# IRQF103C8.net
KiCad netlist of a schematic drawn in EAGLE
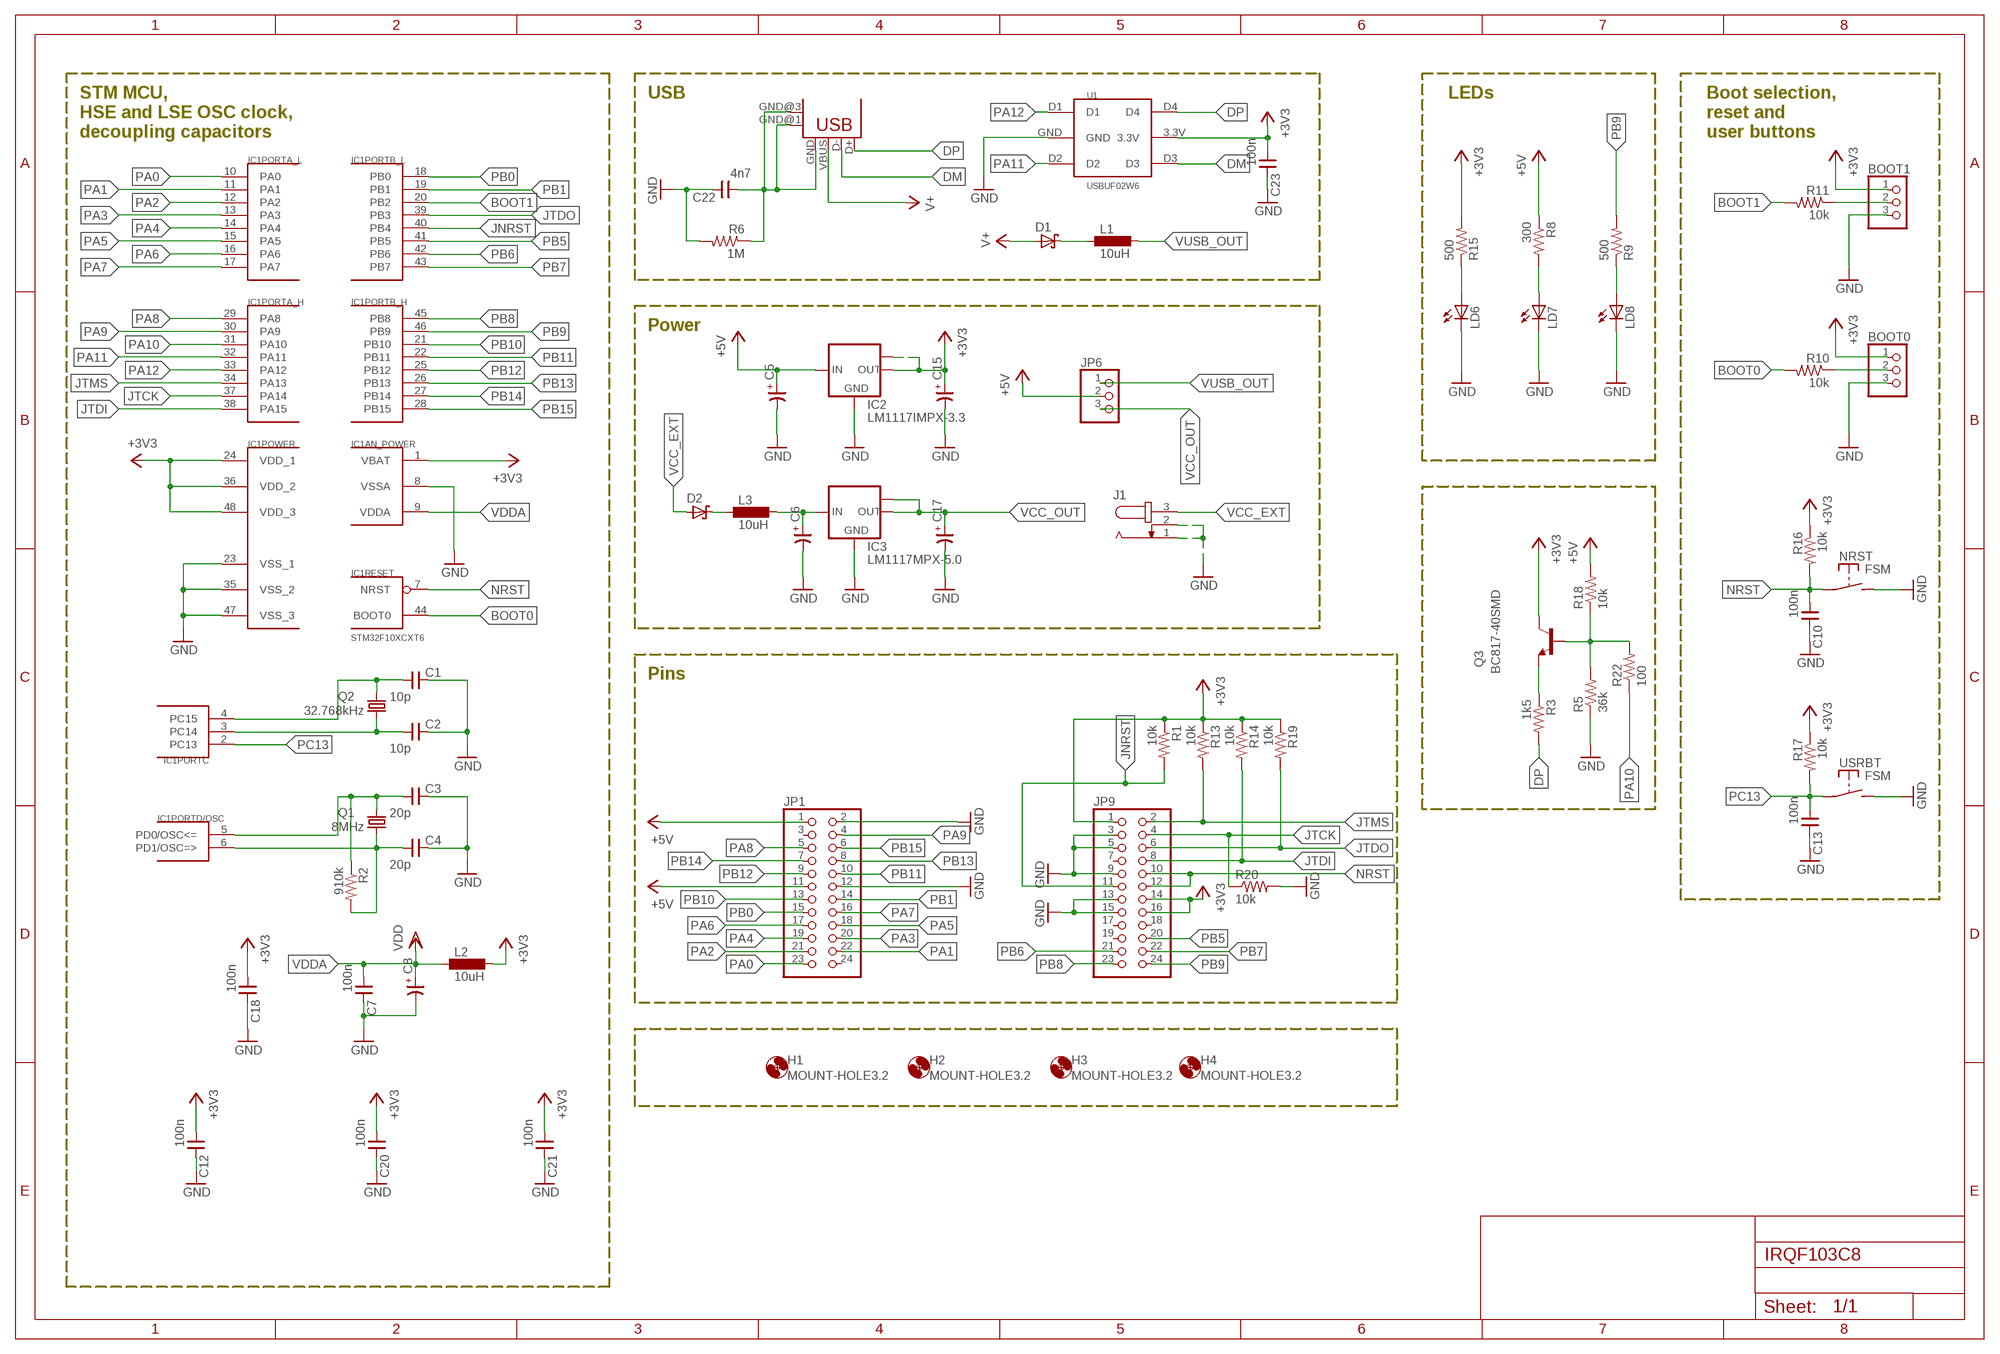
[diagram p0: schematic, sheet 1]

(export (version "E")
  (design (tool "Eeschema 10.0.6"))
  (components
    (comp (ref "BOOT0")
      (value "PINHD-1X3")
      (footprint "eagle-import:1X03")
      (libsource (lib "eagle-import") (part "PINHD-1X3"))
    )
    (comp (ref "BOOT1")
      (value "PINHD-1X3")
      (footprint "eagle-import:1X03")
      (libsource (lib "eagle-import") (part "PINHD-1X3"))
    )
    (comp (ref "C1")
      (value "10p")
      (footprint "eagle-import:0805")
      (libsource (lib "eagle-import") (part "CNP-0805"))
    )
    (comp (ref "C2")
      (value "10p")
      (footprint "eagle-import:0805")
      (libsource (lib "eagle-import") (part "CNP-0805"))
    )
    (comp (ref "C3")
      (value "20p")
      (footprint "eagle-import:0805")
      (libsource (lib "eagle-import") (part "CNP-0805"))
    )
    (comp (ref "C4")
      (value "20p")
      (footprint "eagle-import:0805")
      (libsource (lib "eagle-import") (part "CNP-0805"))
    )
    (comp (ref "C5")
      (value "CP-3258-TE-B")
      (footprint "eagle-import:3528-TE-B")
      (libsource (lib "eagle-import") (part "CP-3258-TE-B"))
    )
    (comp (ref "C6")
      (value "CP-3258-TE-B")
      (footprint "eagle-import:3528-TE-B")
      (libsource (lib "eagle-import") (part "CP-3258-TE-B"))
    )
    (comp (ref "C7")
      (value "100n")
      (footprint "eagle-import:0805")
      (libsource (lib "eagle-import") (part "CNP-0805"))
    )
    (comp (ref "C8")
      (value "CP-3216")
      (footprint "eagle-import:3216_T")
      (libsource (lib "eagle-import") (part "CP-3216"))
    )
    (comp (ref "C10")
      (value "100n")
      (footprint "eagle-import:0805")
      (libsource (lib "eagle-import") (part "CNP-0805"))
    )
    (comp (ref "C12")
      (value "100n")
      (footprint "eagle-import:0805")
      (libsource (lib "eagle-import") (part "CNP-0805"))
    )
    (comp (ref "C13")
      (value "100n")
      (footprint "eagle-import:0805")
      (libsource (lib "eagle-import") (part "CNP-0805"))
    )
    (comp (ref "C15")
      (value "CP-3216-TE-A")
      (footprint "eagle-import:3216-TE-A")
      (libsource (lib "eagle-import") (part "CP-3216-TE-A"))
    )
    (comp (ref "C17")
      (value "CP-3216-TE-A")
      (footprint "eagle-import:3216-TE-A")
      (libsource (lib "eagle-import") (part "CP-3216-TE-A"))
    )
    (comp (ref "C18")
      (value "100n")
      (footprint "eagle-import:0805")
      (libsource (lib "eagle-import") (part "CNP-0805"))
    )
    (comp (ref "C20")
      (value "100n")
      (footprint "eagle-import:0805")
      (libsource (lib "eagle-import") (part "CNP-0805"))
    )
    (comp (ref "C21")
      (value "100n")
      (footprint "eagle-import:0805")
      (libsource (lib "eagle-import") (part "CNP-0805"))
    )
    (comp (ref "C22")
      (value "4n7")
      (footprint "eagle-import:0805")
      (libsource (lib "eagle-import") (part "CNP-0805"))
    )
    (comp (ref "C23")
      (value "100n")
      (footprint "eagle-import:0805")
      (libsource (lib "eagle-import") (part "CNP-0805"))
    )
    (comp (ref "D1")
      (value "SCHOTTKY_SMA")
      (footprint "eagle-import:DIOM5326X292N")
      (libsource (lib "eagle-import") (part "SCHOTTKY_SMA"))
    )
    (comp (ref "D2")
      (value "SCHOTTKY_SMA")
      (footprint "eagle-import:DIOM5326X292N")
      (libsource (lib "eagle-import") (part "SCHOTTKY_SMA"))
    )
    (comp (ref "H1")
      (value "MOUNT-HOLE3.2")
      (footprint "eagle-import:3,2")
      (libsource (lib "eagle-import") (part "MOUNT-HOLE3.2"))
    )
    (comp (ref "H2")
      (value "MOUNT-HOLE3.2")
      (footprint "eagle-import:3,2")
      (libsource (lib "eagle-import") (part "MOUNT-HOLE3.2"))
    )
    (comp (ref "H3")
      (value "MOUNT-HOLE3.2")
      (footprint "eagle-import:3,2")
      (libsource (lib "eagle-import") (part "MOUNT-HOLE3.2"))
    )
    (comp (ref "H4")
      (value "MOUNT-HOLE3.2")
      (footprint "eagle-import:3,2")
      (libsource (lib "eagle-import") (part "MOUNT-HOLE3.2"))
    )
    (comp (ref "IC1")
      (value "STM32F10XCXT6")
      (footprint "eagle-import:TQFP48")
      (libsource (lib "eagle-import") (part "STM32F10XCXT6"))
    )
    (comp (ref "IC2")
      (value "LM1117IMPX-3.3")
      (footprint "eagle-import:SOT223")
      (libsource (lib "eagle-import") (part "LM1117IMPX-3.3"))
    )
    (comp (ref "IC3")
      (value "LM1117MPX-5.0")
      (footprint "eagle-import:SOT223")
      (libsource (lib "eagle-import") (part "LM1117MPX-5.0"))
    )
    (comp (ref "J1")
      (value "JACK-PLUG1")
      (footprint "eagle-import:SPC4078")
      (libsource (lib "eagle-import") (part "JACK-PLUG1"))
    )
    (comp (ref "JP1")
      (value "PINHD-2X12")
      (footprint "eagle-import:2X12")
      (libsource (lib "eagle-import") (part "PINHD-2X12"))
    )
    (comp (ref "JP6")
      (value "PINHD-1X3")
      (footprint "eagle-import:1X03")
      (libsource (lib "eagle-import") (part "PINHD-1X3"))
    )
    (comp (ref "JP9")
      (value "PINHD-2X12")
      (footprint "eagle-import:2X12")
      (libsource (lib "eagle-import") (part "PINHD-2X12"))
    )
    (comp (ref "L1")
      (value "10uH")
      (footprint "eagle-import:INDC1608X95N")
      (libsource (lib "eagle-import") (part "INDUCTOR_0603"))
    )
    (comp (ref "L2")
      (value "10uH")
      (footprint "eagle-import:INDC1608X95N")
      (libsource (lib "eagle-import") (part "INDUCTOR_0603"))
    )
    (comp (ref "L3")
      (value "10uH")
      (footprint "eagle-import:INDC1608X95N")
      (libsource (lib "eagle-import") (part "INDUCTOR_0603"))
    )
    (comp (ref "LD6")
      (value "LEDCHIPLED_0805")
      (footprint "eagle-import:CHIPLED_0805")
      (libsource (lib "eagle-import") (part "LEDCHIPLED_0805"))
    )
    (comp (ref "LD7")
      (value "LEDCHIPLED_0805")
      (footprint "eagle-import:CHIPLED_0805")
      (libsource (lib "eagle-import") (part "LEDCHIPLED_0805"))
    )
    (comp (ref "LD8")
      (value "LEDCHIPLED_0805")
      (footprint "eagle-import:CHIPLED_0805")
      (libsource (lib "eagle-import") (part "LEDCHIPLED_0805"))
    )
    (comp (ref "NRST")
      (value "FSM")
      (footprint "eagle-import:FSM")
      (libsource (lib "eagle-import") (part "FSM"))
    )
    (comp (ref "Q1")
      (value "8MHz")
      (footprint "eagle-import:HC49_S")
      (libsource (lib "eagle-import") (part "CRYTALHC49S"))
    )
    (comp (ref "Q2")
      (value "32.768kHz")
      (footprint "eagle-import:TC26H")
      (libsource (lib "eagle-import") (part "CRYTALTC26H"))
    )
    (comp (ref "Q3")
      (value "BC817-40SMD")
      (footprint "eagle-import:SOT23-BEC")
      (libsource (lib "eagle-import") (part "BC817SMD-40"))
    )
    (comp (ref "R1")
      (value "10k")
      (footprint "eagle-import:M0805")
      (libsource (lib "eagle-import") (part "R-US_M0805"))
    )
    (comp (ref "R2")
      (value "910k")
      (footprint "eagle-import:M0805")
      (libsource (lib "eagle-import") (part "R-US_M0805"))
    )
    (comp (ref "R3")
      (value "1k5")
      (footprint "eagle-import:M0805")
      (libsource (lib "eagle-import") (part "R-US_M0805"))
    )
    (comp (ref "R5")
      (value "36k")
      (footprint "eagle-import:M0805")
      (libsource (lib "eagle-import") (part "R-US_M0805"))
    )
    (comp (ref "R6")
      (value "1M")
      (footprint "eagle-import:M0805")
      (libsource (lib "eagle-import") (part "R-US_M0805"))
    )
    (comp (ref "R8")
      (value "300")
      (footprint "eagle-import:M0805")
      (libsource (lib "eagle-import") (part "R-US_M0805"))
    )
    (comp (ref "R9")
      (value "500")
      (footprint "eagle-import:M0805")
      (libsource (lib "eagle-import") (part "R-US_M0805"))
    )
    (comp (ref "R10")
      (value "10k")
      (footprint "eagle-import:M0805")
      (libsource (lib "eagle-import") (part "R-US_M0805"))
    )
    (comp (ref "R11")
      (value "10k")
      (footprint "eagle-import:M0805")
      (libsource (lib "eagle-import") (part "R-US_M0805"))
    )
    (comp (ref "R13")
      (value "10k")
      (footprint "eagle-import:M0805")
      (libsource (lib "eagle-import") (part "R-US_M0805"))
    )
    (comp (ref "R14")
      (value "10k")
      (footprint "eagle-import:M0805")
      (libsource (lib "eagle-import") (part "R-US_M0805"))
    )
    (comp (ref "R15")
      (value "500")
      (footprint "eagle-import:M0805")
      (libsource (lib "eagle-import") (part "R-US_M0805"))
    )
    (comp (ref "R16")
      (value "10k")
      (footprint "eagle-import:M0805")
      (libsource (lib "eagle-import") (part "R-US_M0805"))
    )
    (comp (ref "R17")
      (value "10k")
      (footprint "eagle-import:M0805")
      (libsource (lib "eagle-import") (part "R-US_M0805"))
    )
    (comp (ref "R18")
      (value "10k")
      (footprint "eagle-import:M0805")
      (libsource (lib "eagle-import") (part "R-US_M0805"))
    )
    (comp (ref "R19")
      (value "10k")
      (footprint "eagle-import:M0805")
      (libsource (lib "eagle-import") (part "R-US_M0805"))
    )
    (comp (ref "R20")
      (value "10k")
      (footprint "eagle-import:M0805")
      (libsource (lib "eagle-import") (part "R-US_M0805"))
    )
    (comp (ref "R22")
      (value "100")
      (footprint "eagle-import:M0805")
      (libsource (lib "eagle-import") (part "R-US_M0805"))
    )
    (comp (ref "U1")
      (value "USBUF02W6")
      (footprint "eagle-import:SOT23-6L")
      (libsource (lib "eagle-import") (part "USBUF02W6"))
    )
    (comp (ref "USB1")
      (value "USB-MB-S")
      (footprint "eagle-import:USB-MB-S")
      (libsource (lib "eagle-import") (part "USB-MB-S"))
    )
    (comp (ref "USRBT")
      (value "FSM")
      (footprint "eagle-import:FSM")
      (libsource (lib "eagle-import") (part "FSM"))
    )
  )
  (nets
    (net (code "1") (name "+3V3") (class "Default")
      (node (ref "BOOT0") (pin "1") (pinfunction "1_1") (pintype "passive"))
      (node (ref "BOOT1") (pin "1") (pinfunction "1_1") (pintype "passive"))
      (node (ref "C12") (pin "1") (pinfunction "1_1") (pintype "passive"))
      (node (ref "C15") (pin "+") (pinfunction "+_+") (pintype "passive"))
      (node (ref "C18") (pin "1") (pinfunction "1_1") (pintype "passive"))
      (node (ref "C20") (pin "1") (pinfunction "1_1") (pintype "passive"))
      (node (ref "C21") (pin "1") (pinfunction "1_1") (pintype "passive"))
      (node (ref "C23") (pin "1") (pinfunction "1_1") (pintype "passive"))
      (node (ref "IC1") (pin "1") (pinfunction "VBAT_1") (pintype "power_in"))
      (node (ref "IC1") (pin "24") (pinfunction "VDD_1_24") (pintype "power_in"))
      (node (ref "IC1") (pin "36") (pinfunction "VDD_2_36") (pintype "power_in"))
      (node (ref "IC1") (pin "48") (pinfunction "VDD_3_48") (pintype "power_in"))
      (node (ref "IC2") (pin "2") (pinfunction "OUT_2") (pintype "passive"))
      (node (ref "IC2") (pin "TAB") (pinfunction "OUT1_TAB") (pintype "passive"))
      (node (ref "JP9") (pin "1") (pinfunction "1_1") (pintype "passive"))
      (node (ref "JP9") (pin "14") (pinfunction "14_14") (pintype "passive"))
      (node (ref "JP9") (pin "16") (pinfunction "16_16") (pintype "passive"))
      (node (ref "L2") (pin "2") (pinfunction "2_2") (pintype "passive"))
      (node (ref "Q3") (pin "C") (pinfunction "C_C") (pintype "passive"))
      (node (ref "R1") (pin "1") (pinfunction "1_1") (pintype "passive"))
      (node (ref "R13") (pin "1") (pinfunction "1_1") (pintype "passive"))
      (node (ref "R14") (pin "1") (pinfunction "1_1") (pintype "passive"))
      (node (ref "R15") (pin "2") (pinfunction "2_2") (pintype "passive"))
      (node (ref "R16") (pin "1") (pinfunction "1_1") (pintype "passive"))
      (node (ref "R17") (pin "1") (pinfunction "1_1") (pintype "passive"))
      (node (ref "R19") (pin "1") (pinfunction "1_1") (pintype "passive"))
      (node (ref "U1") (pin "3.3V") (pinfunction "3.3V_3.3V") (pintype "bidirectional"))
    )
    (net (code "2") (name "+5V") (class "Default")
      (node (ref "C5") (pin "+") (pinfunction "+_+") (pintype "passive"))
      (node (ref "IC2") (pin "3") (pinfunction "IN_3") (pintype "input"))
      (node (ref "JP1") (pin "1") (pinfunction "1_1") (pintype "passive"))
      (node (ref "JP1") (pin "11") (pinfunction "11_11") (pintype "passive"))
      (node (ref "JP6") (pin "2") (pinfunction "2_2") (pintype "passive"))
      (node (ref "R18") (pin "2") (pinfunction "2_2") (pintype "passive"))
      (node (ref "R8") (pin "1") (pinfunction "1_1") (pintype "passive"))
    )
    (net (code "3") (name "BOOT0") (class "Default")
      (node (ref "IC1") (pin "44") (pinfunction "BOOT0_44") (pintype "input"))
      (node (ref "R10") (pin "2") (pinfunction "2_2") (pintype "passive"))
    )
    (net (code "4") (name "BOOT1") (class "Default")
      (node (ref "IC1") (pin "20") (pinfunction "PB2_20") (pintype "bidirectional"))
      (node (ref "R11") (pin "2") (pinfunction "2_2") (pintype "passive"))
    )
    (net (code "5") (name "DM") (class "Default")
      (node (ref "U1") (pin "D3") (pinfunction "D3_D3") (pintype "bidirectional"))
      (node (ref "USB1") (pin "D-") (pinfunction "D-_D-") (pintype "bidirectional"))
    )
    (net (code "6") (name "DP") (class "Default")
      (node (ref "R3") (pin "2") (pinfunction "2_2") (pintype "passive"))
      (node (ref "U1") (pin "D4") (pinfunction "D4_D4") (pintype "bidirectional"))
      (node (ref "USB1") (pin "D+") (pinfunction "D+_D+") (pintype "bidirectional"))
    )
    (net (code "7") (name "GND") (class "Default")
      (node (ref "BOOT0") (pin "3") (pinfunction "3_3") (pintype "passive"))
      (node (ref "BOOT1") (pin "3") (pinfunction "3_3") (pintype "passive"))
      (node (ref "C1") (pin "2") (pinfunction "2_2") (pintype "passive"))
      (node (ref "C10") (pin "2") (pinfunction "2_2") (pintype "passive"))
      (node (ref "C12") (pin "2") (pinfunction "2_2") (pintype "passive"))
      (node (ref "C13") (pin "2") (pinfunction "2_2") (pintype "passive"))
      (node (ref "C15") (pin "-") (pinfunction "-_-") (pintype "passive"))
      (node (ref "C17") (pin "-") (pinfunction "-_-") (pintype "passive"))
      (node (ref "C18") (pin "2") (pinfunction "2_2") (pintype "passive"))
      (node (ref "C2") (pin "2") (pinfunction "2_2") (pintype "passive"))
      (node (ref "C20") (pin "2") (pinfunction "2_2") (pintype "passive"))
      (node (ref "C21") (pin "2") (pinfunction "2_2") (pintype "passive"))
      (node (ref "C22") (pin "2") (pinfunction "2_2") (pintype "passive"))
      (node (ref "C23") (pin "2") (pinfunction "2_2") (pintype "passive"))
      (node (ref "C3") (pin "2") (pinfunction "2_2") (pintype "passive"))
      (node (ref "C4") (pin "2") (pinfunction "2_2") (pintype "passive"))
      (node (ref "C5") (pin "-") (pinfunction "-_-") (pintype "passive"))
      (node (ref "C6") (pin "-") (pinfunction "-_-") (pintype "passive"))
      (node (ref "C7") (pin "2") (pinfunction "2_2") (pintype "passive"))
      (node (ref "C8") (pin "-") (pinfunction "-_-") (pintype "passive"))
      (node (ref "IC1") (pin "23") (pinfunction "VSS_1_23") (pintype "power_in"))
      (node (ref "IC1") (pin "35") (pinfunction "VSS_2_35") (pintype "power_in"))
      (node (ref "IC1") (pin "47") (pinfunction "VSS_3_47") (pintype "power_in"))
      (node (ref "IC1") (pin "8") (pinfunction "VSSA_8") (pintype "power_in"))
      (node (ref "IC2") (pin "1") (pinfunction "GND_1") (pintype "input"))
      (node (ref "IC3") (pin "1") (pinfunction "GND_1") (pintype "input"))
      (node (ref "J1") (pin "1") (pinfunction "1_1") (pintype "passive"))
      (node (ref "J1") (pin "2") (pinfunction "2_2") (pintype "passive"))
      (node (ref "JP1") (pin "12") (pinfunction "12_12") (pintype "passive"))
      (node (ref "JP1") (pin "2") (pinfunction "2_2") (pintype "passive"))
      (node (ref "JP9") (pin "13") (pinfunction "13_13") (pintype "passive"))
      (node (ref "JP9") (pin "15") (pinfunction "15_15") (pintype "passive"))
      (node (ref "JP9") (pin "3") (pinfunction "3_3") (pintype "passive"))
      (node (ref "JP9") (pin "5") (pinfunction "5_5") (pintype "passive"))
      (node (ref "JP9") (pin "9") (pinfunction "9_9") (pintype "passive"))
      (node (ref "LD6") (pin "C") (pinfunction "C_C") (pintype "passive"))
      (node (ref "LD7") (pin "C") (pinfunction "C_C") (pintype "passive"))
      (node (ref "LD8") (pin "C") (pinfunction "C_C") (pintype "passive"))
      (node (ref "NRST") (pin "P$2") (pinfunction "S_P$2") (pintype "passive"))
      (node (ref "R20") (pin "2") (pinfunction "2_2") (pintype "passive"))
      (node (ref "R5") (pin "1") (pinfunction "1_1") (pintype "passive"))
      (node (ref "R6") (pin "2") (pinfunction "2_2") (pintype "passive"))
      (node (ref "U1") (pin "GND") (pinfunction "GND_GND") (pintype "bidirectional"))
      (node (ref "USRBT") (pin "P$2") (pinfunction "S_P$2") (pintype "passive"))
    )
    (net (code "8") (name "JNRST") (class "Default")
      (node (ref "IC1") (pin "40") (pinfunction "PB4_40") (pintype "bidirectional"))
      (node (ref "JP9") (pin "11") (pinfunction "11_11") (pintype "passive"))
      (node (ref "R1") (pin "2") (pinfunction "2_2") (pintype "passive"))
    )
    (net (code "9") (name "JTCK") (class "Default")
      (node (ref "IC1") (pin "37") (pinfunction "PA14_37") (pintype "bidirectional"))
      (node (ref "JP9") (pin "4") (pinfunction "4_4") (pintype "passive"))
      (node (ref "R20") (pin "1") (pinfunction "1_1") (pintype "passive"))
    )
    (net (code "10") (name "JTDI") (class "Default")
      (node (ref "IC1") (pin "38") (pinfunction "PA15_38") (pintype "bidirectional"))
      (node (ref "JP9") (pin "8") (pinfunction "8_8") (pintype "passive"))
      (node (ref "R14") (pin "2") (pinfunction "2_2") (pintype "passive"))
    )
    (net (code "11") (name "JTDO") (class "Default")
      (node (ref "IC1") (pin "39") (pinfunction "PB3_39") (pintype "bidirectional"))
      (node (ref "JP9") (pin "6") (pinfunction "6_6") (pintype "passive"))
      (node (ref "R19") (pin "2") (pinfunction "2_2") (pintype "passive"))
    )
    (net (code "12") (name "JTMS") (class "Default")
      (node (ref "IC1") (pin "34") (pinfunction "PA13_34") (pintype "bidirectional"))
      (node (ref "JP9") (pin "2") (pinfunction "2_2") (pintype "passive"))
      (node (ref "R13") (pin "2") (pinfunction "2_2") (pintype "passive"))
    )
    (net (code "13") (name "NRST") (class "Default")
      (node (ref "C10") (pin "1") (pinfunction "1_1") (pintype "passive"))
      (node (ref "IC1") (pin "7") (pinfunction "NRST_7") (pintype "input"))
      (node (ref "JP9") (pin "10") (pinfunction "10_10") (pintype "passive"))
      (node (ref "JP9") (pin "12") (pinfunction "12_12") (pintype "passive"))
      (node (ref "NRST") (pin "P$1") (pinfunction "P_P$1") (pintype "passive"))
      (node (ref "R16") (pin "2") (pinfunction "2_2") (pintype "passive"))
    )
    (net (code "14") (name "Net-(BOOT0-Pad2)") (class "Default")
      (node (ref "BOOT0") (pin "2") (pinfunction "2_2") (pintype "passive"))
      (node (ref "R10") (pin "1") (pinfunction "1_1") (pintype "passive"))
    )
    (net (code "15") (name "Net-(BOOT1-Pad2)") (class "Default")
      (node (ref "BOOT1") (pin "2") (pinfunction "2_2") (pintype "passive"))
      (node (ref "R11") (pin "1") (pinfunction "1_1") (pintype "passive"))
    )
    (net (code "16") (name "Net-(C22-Pad1)") (class "Default")
      (node (ref "C22") (pin "1") (pinfunction "1_1") (pintype "passive"))
      (node (ref "R6") (pin "1") (pinfunction "1_1") (pintype "passive"))
      (node (ref "USB1") (pin "GND") (pinfunction "GND_GND") (pintype "bidirectional"))
      (node (ref "USB1") (pin "GND@1") (pinfunction "GND_GND@1") (pintype "bidirectional"))
      (node (ref "USB1") (pin "GND@3") (pinfunction "GND_GND@3") (pintype "bidirectional"))
    )
    (net (code "17") (name "Net-(D1-PadK)") (class "Default")
      (node (ref "D1") (pin "K") (pinfunction "K_K") (pintype "passive"))
      (node (ref "L1") (pin "1") (pinfunction "1_1") (pintype "passive"))
    )
    (net (code "18") (name "Net-(D2-PadK)") (class "Default")
      (node (ref "D2") (pin "K") (pinfunction "K_K") (pintype "passive"))
      (node (ref "L3") (pin "1") (pinfunction "1_1") (pintype "passive"))
    )
    (net (code "19") (name "Net-(IC1F-PC14)") (class "Default")
      (node (ref "C2") (pin "1") (pinfunction "1_1") (pintype "passive"))
      (node (ref "IC1") (pin "3") (pinfunction "PC14_3") (pintype "bidirectional"))
      (node (ref "Q2") (pin "1") (pinfunction "1_1") (pintype "passive"))
    )
    (net (code "20") (name "Net-(IC1F-PC15)") (class "Default")
      (node (ref "C1") (pin "1") (pinfunction "1_1") (pintype "passive"))
      (node (ref "IC1") (pin "4") (pinfunction "PC15_4") (pintype "bidirectional"))
      (node (ref "Q2") (pin "2") (pinfunction "2_2") (pintype "passive"))
    )
    (net (code "21") (name "Net-(IC1G-PD0{slash}OSC<=)") (class "Default")
      (node (ref "C3") (pin "1") (pinfunction "1_1") (pintype "passive"))
      (node (ref "IC1") (pin "5") (pinfunction "PD0/OSC<=_5") (pintype "bidirectional"))
      (node (ref "Q1") (pin "2") (pinfunction "2_2") (pintype "passive"))
      (node (ref "R2") (pin "1") (pinfunction "1_1") (pintype "passive"))
    )
    (net (code "22") (name "Net-(IC1G-PD1{slash}OSC=>)") (class "Default")
      (node (ref "C4") (pin "1") (pinfunction "1_1") (pintype "passive"))
      (node (ref "IC1") (pin "6") (pinfunction "PD1/OSC=>_6") (pintype "bidirectional"))
      (node (ref "Q1") (pin "1") (pinfunction "1_1") (pintype "passive"))
      (node (ref "R2") (pin "2") (pinfunction "2_2") (pintype "passive"))
    )
    (net (code "23") (name "Net-(IC3-IN)") (class "Default")
      (node (ref "C6") (pin "+") (pinfunction "+_+") (pintype "passive"))
      (node (ref "IC3") (pin "3") (pinfunction "IN_3") (pintype "input"))
      (node (ref "L3") (pin "2") (pinfunction "2_2") (pintype "passive"))
    )
    (net (code "24") (name "Net-(LD6-PadA)") (class "Default")
      (node (ref "LD6") (pin "A") (pinfunction "A_A") (pintype "passive"))
      (node (ref "R15") (pin "1") (pinfunction "1_1") (pintype "passive"))
    )
    (net (code "25") (name "Net-(LD7-PadA)") (class "Default")
      (node (ref "LD7") (pin "A") (pinfunction "A_A") (pintype "passive"))
      (node (ref "R8") (pin "2") (pinfunction "2_2") (pintype "passive"))
    )
    (net (code "26") (name "Net-(LD8-PadA)") (class "Default")
      (node (ref "LD8") (pin "A") (pinfunction "A_A") (pintype "passive"))
      (node (ref "R9") (pin "1") (pinfunction "1_1") (pintype "passive"))
    )
    (net (code "27") (name "Net-(Q3-PadB)") (class "Default")
      (node (ref "Q3") (pin "B") (pinfunction "B_B") (pintype "passive"))
      (node (ref "R18") (pin "1") (pinfunction "1_1") (pintype "passive"))
      (node (ref "R22") (pin "2") (pinfunction "2_2") (pintype "passive"))
      (node (ref "R5") (pin "2") (pinfunction "2_2") (pintype "passive"))
    )
    (net (code "28") (name "Net-(Q3-PadE)") (class "Default")
      (node (ref "Q3") (pin "E") (pinfunction "E_E") (pintype "passive"))
      (node (ref "R3") (pin "1") (pinfunction "1_1") (pintype "passive"))
    )
    (net (code "29") (name "PA0") (class "Default")
      (node (ref "IC1") (pin "10") (pinfunction "PA0_10") (pintype "bidirectional"))
      (node (ref "JP1") (pin "23") (pinfunction "23_23") (pintype "passive"))
    )
    (net (code "30") (name "PA1") (class "Default")
      (node (ref "IC1") (pin "11") (pinfunction "PA1_11") (pintype "bidirectional"))
      (node (ref "JP1") (pin "22") (pinfunction "22_22") (pintype "passive"))
    )
    (net (code "31") (name "PA2") (class "Default")
      (node (ref "IC1") (pin "12") (pinfunction "PA2_12") (pintype "bidirectional"))
      (node (ref "JP1") (pin "21") (pinfunction "21_21") (pintype "passive"))
    )
    (net (code "32") (name "PA3") (class "Default")
      (node (ref "IC1") (pin "13") (pinfunction "PA3_13") (pintype "bidirectional"))
      (node (ref "JP1") (pin "20") (pinfunction "20_20") (pintype "passive"))
    )
    (net (code "33") (name "PA4") (class "Default")
      (node (ref "IC1") (pin "14") (pinfunction "PA4_14") (pintype "bidirectional"))
      (node (ref "JP1") (pin "19") (pinfunction "19_19") (pintype "passive"))
    )
    (net (code "34") (name "PA5") (class "Default")
      (node (ref "IC1") (pin "15") (pinfunction "PA5_15") (pintype "bidirectional"))
      (node (ref "JP1") (pin "18") (pinfunction "18_18") (pintype "passive"))
    )
    (net (code "35") (name "PA6") (class "Default")
      (node (ref "IC1") (pin "16") (pinfunction "PA6_16") (pintype "bidirectional"))
      (node (ref "JP1") (pin "17") (pinfunction "17_17") (pintype "passive"))
    )
    (net (code "36") (name "PA7") (class "Default")
      (node (ref "IC1") (pin "17") (pinfunction "PA7_17") (pintype "bidirectional"))
      (node (ref "JP1") (pin "16") (pinfunction "16_16") (pintype "passive"))
    )
    (net (code "37") (name "PA8") (class "Default")
      (node (ref "IC1") (pin "29") (pinfunction "PA8_29") (pintype "bidirectional"))
      (node (ref "JP1") (pin "5") (pinfunction "5_5") (pintype "passive"))
    )
    (net (code "38") (name "PA9") (class "Default")
      (node (ref "IC1") (pin "30") (pinfunction "PA9_30") (pintype "bidirectional"))
      (node (ref "JP1") (pin "4") (pinfunction "4_4") (pintype "passive"))
    )
    (net (code "39") (name "PA10") (class "Default")
      (node (ref "IC1") (pin "31") (pinfunction "PA10_31") (pintype "bidirectional"))
      (node (ref "R22") (pin "1") (pinfunction "1_1") (pintype "passive"))
    )
    (net (code "40") (name "PA11") (class "Default")
      (node (ref "IC1") (pin "32") (pinfunction "PA11_32") (pintype "bidirectional"))
      (node (ref "U1") (pin "D2") (pinfunction "D2_D2") (pintype "bidirectional"))
    )
    (net (code "41") (name "PA12") (class "Default")
      (node (ref "IC1") (pin "33") (pinfunction "PA12_33") (pintype "bidirectional"))
      (node (ref "U1") (pin "D1") (pinfunction "D1_D1") (pintype "bidirectional"))
    )
    (net (code "42") (name "PB0") (class "Default")
      (node (ref "IC1") (pin "18") (pinfunction "PB0_18") (pintype "bidirectional"))
      (node (ref "JP1") (pin "15") (pinfunction "15_15") (pintype "passive"))
    )
    (net (code "43") (name "PB1") (class "Default")
      (node (ref "IC1") (pin "19") (pinfunction "PB1_19") (pintype "bidirectional"))
      (node (ref "JP1") (pin "14") (pinfunction "14_14") (pintype "passive"))
    )
    (net (code "44") (name "PB5") (class "Default")
      (node (ref "IC1") (pin "41") (pinfunction "PB5_41") (pintype "bidirectional"))
      (node (ref "JP9") (pin "20") (pinfunction "20_20") (pintype "passive"))
    )
    (net (code "45") (name "PB6") (class "Default")
      (node (ref "IC1") (pin "42") (pinfunction "PB6_42") (pintype "bidirectional"))
      (node (ref "JP9") (pin "21") (pinfunction "21_21") (pintype "passive"))
    )
    (net (code "46") (name "PB7") (class "Default")
      (node (ref "IC1") (pin "43") (pinfunction "PB7_43") (pintype "bidirectional"))
      (node (ref "JP9") (pin "22") (pinfunction "22_22") (pintype "passive"))
    )
    (net (code "47") (name "PB8") (class "Default")
      (node (ref "IC1") (pin "45") (pinfunction "PB8_45") (pintype "bidirectional"))
      (node (ref "JP9") (pin "23") (pinfunction "23_23") (pintype "passive"))
    )
    (net (code "48") (name "PB9") (class "Default")
      (node (ref "IC1") (pin "46") (pinfunction "PB9_46") (pintype "bidirectional"))
      (node (ref "JP9") (pin "24") (pinfunction "24_24") (pintype "passive"))
      (node (ref "R9") (pin "2") (pinfunction "2_2") (pintype "passive"))
    )
    (net (code "49") (name "PB10") (class "Default")
      (node (ref "IC1") (pin "21") (pinfunction "PB10_21") (pintype "bidirectional"))
      (node (ref "JP1") (pin "13") (pinfunction "13_13") (pintype "passive"))
    )
    (net (code "50") (name "PB11") (class "Default")
      (node (ref "IC1") (pin "22") (pinfunction "PB11_22") (pintype "bidirectional"))
      (node (ref "JP1") (pin "10") (pinfunction "10_10") (pintype "passive"))
    )
    (net (code "51") (name "PB12") (class "Default")
      (node (ref "IC1") (pin "25") (pinfunction "PB12_25") (pintype "bidirectional"))
      (node (ref "JP1") (pin "9") (pinfunction "9_9") (pintype "passive"))
    )
    (net (code "52") (name "PB13") (class "Default")
      (node (ref "IC1") (pin "26") (pinfunction "PB13_26") (pintype "bidirectional"))
      (node (ref "JP1") (pin "8") (pinfunction "8_8") (pintype "passive"))
    )
    (net (code "53") (name "PB14") (class "Default")
      (node (ref "IC1") (pin "27") (pinfunction "PB14_27") (pintype "bidirectional"))
      (node (ref "JP1") (pin "7") (pinfunction "7_7") (pintype "passive"))
    )
    (net (code "54") (name "PB15") (class "Default")
      (node (ref "IC1") (pin "28") (pinfunction "PB15_28") (pintype "bidirectional"))
      (node (ref "JP1") (pin "6") (pinfunction "6_6") (pintype "passive"))
    )
    (net (code "55") (name "PC13") (class "Default")
      (node (ref "C13") (pin "1") (pinfunction "1_1") (pintype "passive"))
      (node (ref "IC1") (pin "2") (pinfunction "PC13_2") (pintype "bidirectional"))
      (node (ref "R17") (pin "2") (pinfunction "2_2") (pintype "passive"))
      (node (ref "USRBT") (pin "P$1") (pinfunction "P_P$1") (pintype "passive"))
    )
    (net (code "56") (name "V+") (class "Default")
      (node (ref "D1") (pin "A") (pinfunction "A_A") (pintype "passive"))
      (node (ref "USB1") (pin "VBUS") (pinfunction "VBUS_VBUS") (pintype "bidirectional"))
    )
    (net (code "57") (name "VCC_EXT") (class "Default")
      (node (ref "D2") (pin "A") (pinfunction "A_A") (pintype "passive"))
      (node (ref "J1") (pin "3") (pinfunction "3_3") (pintype "passive"))
    )
    (net (code "58") (name "VCC_OUT") (class "Default")
      (node (ref "C17") (pin "+") (pinfunction "+_+") (pintype "passive"))
      (node (ref "IC3") (pin "2") (pinfunction "OUT_2") (pintype "passive"))
      (node (ref "IC3") (pin "TAB") (pinfunction "OUT1_TAB") (pintype "passive"))
      (node (ref "JP6") (pin "3") (pinfunction "3_3") (pintype "passive"))
    )
    (net (code "59") (name "VDDA") (class "Default")
      (node (ref "C7") (pin "1") (pinfunction "1_1") (pintype "passive"))
      (node (ref "C8") (pin "+") (pinfunction "+_+") (pintype "passive"))
      (node (ref "IC1") (pin "9") (pinfunction "VDDA_9") (pintype "power_in"))
      (node (ref "L2") (pin "1") (pinfunction "1_1") (pintype "passive"))
    )
    (net (code "60") (name "VUSB_OUT") (class "Default")
      (node (ref "JP6") (pin "1") (pinfunction "1_1") (pintype "passive"))
      (node (ref "L1") (pin "2") (pinfunction "2_2") (pintype "passive"))
    )
    (net (code "61") (name "unconnected-(JP1-Pad3)") (class "Default")
      (node (ref "JP1") (pin "3") (pinfunction "3_3") (pintype "passive"))
    )
    (net (code "62") (name "unconnected-(JP1-Pad24)") (class "Default")
      (node (ref "JP1") (pin "24") (pinfunction "24_24") (pintype "passive"))
    )
    (net (code "63") (name "unconnected-(JP9-Pad7)") (class "Default")
      (node (ref "JP9") (pin "7") (pinfunction "7_7") (pintype "passive"))
    )
    (net (code "64") (name "unconnected-(JP9-Pad17)") (class "Default")
      (node (ref "JP9") (pin "17") (pinfunction "17_17") (pintype "passive"))
    )
    (net (code "65") (name "unconnected-(JP9-Pad18)") (class "Default")
      (node (ref "JP9") (pin "18") (pinfunction "18_18") (pintype "passive"))
    )
    (net (code "66") (name "unconnected-(JP9-Pad19)") (class "Default")
      (node (ref "JP9") (pin "19") (pinfunction "19_19") (pintype "passive"))
    )
  )
)
